# neodk_v1_2.net
KiCad netlist of a schematic drawn in EAGLE
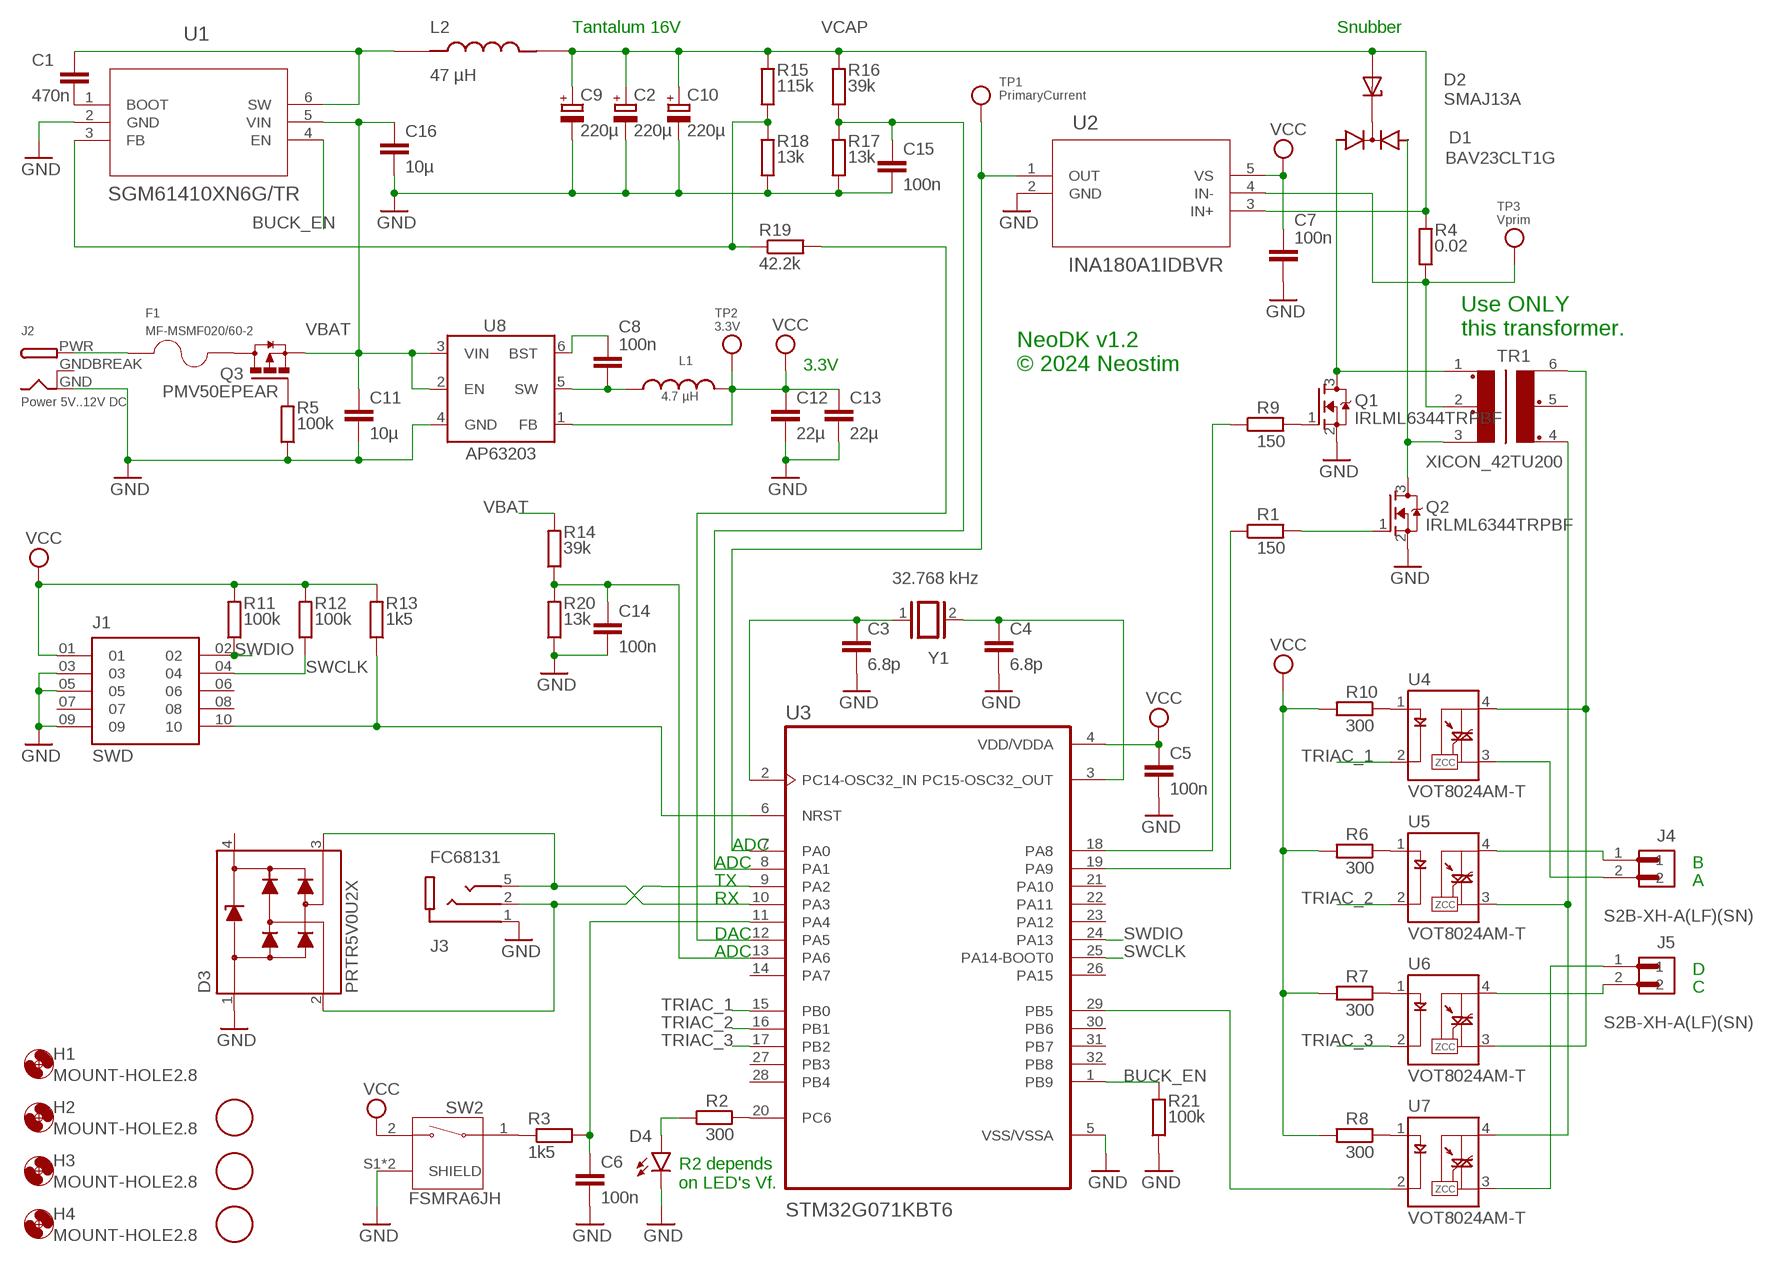
[diagram p0: schematic, sheet 1]

(export (version "E")
  (design (tool "Eeschema 10.0.6"))
  (components
    (comp (ref "C1")
      (value "470n")
      (footprint "eagle-import:C0603")
      (libsource (lib "eagle-import") (part "C-EUC0603"))
    )
    (comp (ref "C2")
      (value "220µ")
      (footprint "eagle-import:SMC_D")
      (fields (field (name "MP") "TPSE227M016R0150"))
      (libsource (lib "eagle-import") (part "CPOL-EUSMCD"))
    )
    (comp (ref "C3")
      (value "6.8p")
      (footprint "eagle-import:C0603")
      (libsource (lib "eagle-import") (part "C-EUC0603"))
    )
    (comp (ref "C4")
      (value "6.8p")
      (footprint "eagle-import:C0603")
      (libsource (lib "eagle-import") (part "C-EUC0603"))
    )
    (comp (ref "C5")
      (value "100n")
      (footprint "eagle-import:C0603")
      (libsource (lib "eagle-import") (part "C-EUC0603"))
    )
    (comp (ref "C6")
      (value "100n")
      (footprint "eagle-import:C0603")
      (libsource (lib "eagle-import") (part "C-EUC0603"))
    )
    (comp (ref "C7")
      (value "100n")
      (footprint "eagle-import:C0603")
      (libsource (lib "eagle-import") (part "C-EUC0603"))
    )
    (comp (ref "C8")
      (value "100n")
      (footprint "eagle-import:C0603")
      (libsource (lib "eagle-import") (part "C-EUC0603"))
    )
    (comp (ref "C9")
      (value "220µ")
      (footprint "eagle-import:SMC_D")
      (fields (field (name "MP") "TPSE227M016R0150"))
      (libsource (lib "eagle-import") (part "CPOL-EUSMCD"))
    )
    (comp (ref "C10")
      (value "220µ")
      (footprint "eagle-import:SMC_D")
      (fields (field (name "MP") "TPSE227M016R0150"))
      (libsource (lib "eagle-import") (part "CPOL-EUSMCD"))
    )
    (comp (ref "C11")
      (value "10µ")
      (footprint "eagle-import:C0603")
      (libsource (lib "eagle-import") (part "C-EUC0603"))
    )
    (comp (ref "C12")
      (value "22µ")
      (footprint "eagle-import:C0603")
      (libsource (lib "eagle-import") (part "C-EUC0603"))
    )
    (comp (ref "C13")
      (value "22µ")
      (footprint "eagle-import:C0603")
      (libsource (lib "eagle-import") (part "C-EUC0603"))
    )
    (comp (ref "C14")
      (value "100n")
      (footprint "eagle-import:C0603")
      (libsource (lib "eagle-import") (part "C-EUC0603"))
    )
    (comp (ref "C15")
      (value "100n")
      (footprint "eagle-import:C0603")
      (libsource (lib "eagle-import") (part "C-EUC0603"))
    )
    (comp (ref "C16")
      (value "10µ")
      (footprint "eagle-import:C0603")
      (libsource (lib "eagle-import") (part "C-EUC0603"))
    )
    (comp (ref "D1")
      (value "BAV23CLT1G")
      (footprint "eagle-import:SOT23")
      (libsource (lib "eagle-import") (part "DIODE-2AC|CASOT23"))
    )
    (comp (ref "D2")
      (value "SMAJ13A")
      (footprint "eagle-import:DIOM4325X250N")
      (fields (field (name "MF") "STMicroelectronics") (field (name "MP") "SMAJ13A-TR"))
      (libsource (lib "eagle-import") (part "SMAJ13A"))
    )
    (comp (ref "D3")
      (value "PRTR5V0U2X")
      (footprint "eagle-import:SOT190P230X110-4N")
      (fields (field (name "MF") "Nexperia USA"))
      (libsource (lib "eagle-import") (part "PRTR5V0U2X"))
    )
    (comp (ref "D4")
      (value "LEDCHIP-LED0805")
      (footprint "eagle-import:CHIP-LED0805")
      (libsource (lib "eagle-import") (part "LEDCHIP-LED0805"))
    )
    (comp (ref "F1")
      (value "MF-MSMF020/60-2")
      (footprint "eagle-import:FUSER_MF-MSMF020_60-2")
      (fields (field (name "MF") "Bourns"))
      (libsource (lib "eagle-import") (part "MF-MSMF020/60-2"))
    )
    (comp (ref "FID1")
      (value "FIDUCIAL")
      (footprint "eagle-import:FIDUCIAL_1MM")
      (libsource (lib "eagle-import") (part "FIDUCIAL"))
    )
    (comp (ref "FID2")
      (value "FIDUCIAL")
      (footprint "eagle-import:FIDUCIAL_1MM")
      (libsource (lib "eagle-import") (part "FIDUCIAL"))
    )
    (comp (ref "FID3")
      (value "FIDUCIAL")
      (footprint "eagle-import:FIDUCIAL_1MM")
      (libsource (lib "eagle-import") (part "FIDUCIAL"))
    )
    (comp (ref "H1")
      (value "MOUNT-HOLE2.8")
      (footprint "eagle-import:2,8")
      (libsource (lib "eagle-import") (part "MOUNT-HOLE2.8"))
    )
    (comp (ref "H2")
      (value "MOUNT-HOLE2.8")
      (footprint "eagle-import:2,8")
      (libsource (lib "eagle-import") (part "MOUNT-HOLE2.8"))
    )
    (comp (ref "H3")
      (value "MOUNT-HOLE2.8")
      (footprint "eagle-import:2,8")
      (libsource (lib "eagle-import") (part "MOUNT-HOLE2.8"))
    )
    (comp (ref "H4")
      (value "MOUNT-HOLE2.8")
      (footprint "eagle-import:2,8")
      (libsource (lib "eagle-import") (part "MOUNT-HOLE2.8"))
    )
    (comp (ref "J1")
      (value "SWD")
      (footprint "eagle-import:SAMTEC_FTSH-105-XX-X-DV")
      (fields (field (name "MF") "Samtec") (field (name "MP") "FTSH-105-01-L-DV"))
      (libsource (lib "eagle-import") (part "FTSH-105-XX-X-DV"))
    )
    (comp (ref "J2")
      (value "Power 5V..12V DC")
      (footprint "eagle-import:DCJACK_2MM_PTH")
      (libsource (lib "eagle-import") (part "DCBARRELPTH"))
    )
    (comp (ref "J3")
      (value "FC68131")
      (footprint "eagle-import:CLIFF_FC68131")
      (fields (field (name "MF") "Cliff"))
      (libsource (lib "eagle-import") (part "FC68131"))
    )
    (comp (ref "J4")
      (value "S2B-XH-A(LF)(SN)")
      (footprint "eagle-import:JST_S2B-XH-A(LF)(SN)")
      (fields (field (name "MF") "JST Sales"))
      (libsource (lib "eagle-import") (part "S2B-XH-A(LF)(SN)"))
    )
    (comp (ref "J5")
      (value "S2B-XH-A(LF)(SN)")
      (footprint "eagle-import:JST_S2B-XH-A(LF)(SN)")
      (fields (field (name "MF") "JST Sales"))
      (libsource (lib "eagle-import") (part "S2B-XH-A(LF)(SN)"))
    )
    (comp (ref "L1")
      (value "4.7 µH")
      (footprint "eagle-import:IND_VLS5045EX-4R7M")
      (fields (field (name "MF") "TDK") (field (name "MP") "VLS5045EX-4R7M"))
      (libsource (lib "eagle-import") (part "VLS5045EX-4R7M"))
    )
    (comp (ref "L2")
      (value "47 µH")
      (footprint "eagle-import:IND_CLF7045NIT-470M-D")
      (fields (field (name "MF") "TDK") (field (name "MP") "CLF7045NIT-470M-D"))
      (libsource (lib "eagle-import") (part "CLF7045NIT-470M-D"))
    )
    (comp (ref "Q1")
      (value "IRLML6344TRPBF")
      (footprint "eagle-import:SOT23")
      (libsource (lib "eagle-import") (part "MOSFET-NREFLOW"))
    )
    (comp (ref "Q2")
      (value "IRLML6344TRPBF")
      (footprint "eagle-import:SOT23")
      (libsource (lib "eagle-import") (part "MOSFET-NREFLOW"))
    )
    (comp (ref "Q3")
      (value "PMV50EPEAR")
      (footprint "eagle-import:SOT23")
      (libsource (lib "eagle-import") (part "PMV50EPEAR"))
    )
    (comp (ref "R1")
      (value "150")
      (footprint "eagle-import:R0603")
      (libsource (lib "eagle-import") (part "R-EU_R0603"))
    )
    (comp (ref "R2")
      (value "300")
      (footprint "eagle-import:R0603")
      (libsource (lib "eagle-import") (part "R-EU_R0603"))
    )
    (comp (ref "R3")
      (value "1k5")
      (footprint "eagle-import:R0603")
      (libsource (lib "eagle-import") (part "R-EU_R0603"))
    )
    (comp (ref "R4")
      (value "0.02")
      (footprint "eagle-import:R1206")
      (libsource (lib "eagle-import") (part "R-EU_R1206"))
    )
    (comp (ref "R5")
      (value "100k")
      (footprint "eagle-import:R0603")
      (libsource (lib "eagle-import") (part "R-EU_R0603"))
    )
    (comp (ref "R6")
      (value "300")
      (footprint "eagle-import:R0603")
      (libsource (lib "eagle-import") (part "R-EU_R0603"))
    )
    (comp (ref "R7")
      (value "300")
      (footprint "eagle-import:R0603")
      (libsource (lib "eagle-import") (part "R-EU_R0603"))
    )
    (comp (ref "R8")
      (value "300")
      (footprint "eagle-import:R0603")
      (libsource (lib "eagle-import") (part "R-EU_R0603"))
    )
    (comp (ref "R9")
      (value "150")
      (footprint "eagle-import:R0603")
      (libsource (lib "eagle-import") (part "R-EU_R0603"))
    )
    (comp (ref "R10")
      (value "300")
      (footprint "eagle-import:R0603")
      (libsource (lib "eagle-import") (part "R-EU_R0603"))
    )
    (comp (ref "R11")
      (value "100k")
      (footprint "eagle-import:R0603")
      (libsource (lib "eagle-import") (part "R-EU_R0603"))
    )
    (comp (ref "R12")
      (value "100k")
      (footprint "eagle-import:R0603")
      (libsource (lib "eagle-import") (part "R-EU_R0603"))
    )
    (comp (ref "R13")
      (value "1k5")
      (footprint "eagle-import:R0603")
      (libsource (lib "eagle-import") (part "R-EU_R0603"))
    )
    (comp (ref "R14")
      (value "39k")
      (footprint "eagle-import:R0603")
      (libsource (lib "eagle-import") (part "R-EU_R0603"))
    )
    (comp (ref "R15")
      (value "115k")
      (footprint "eagle-import:R0603")
      (libsource (lib "eagle-import") (part "R-EU_R0603"))
    )
    (comp (ref "R16")
      (value "39k")
      (footprint "eagle-import:R0603")
      (libsource (lib "eagle-import") (part "R-EU_R0603"))
    )
    (comp (ref "R17")
      (value "13k")
      (footprint "eagle-import:R0603")
      (libsource (lib "eagle-import") (part "R-EU_R0603"))
    )
    (comp (ref "R18")
      (value "13k")
      (footprint "eagle-import:R0603")
      (libsource (lib "eagle-import") (part "R-EU_R0603"))
    )
    (comp (ref "R19")
      (value "42.2k")
      (footprint "eagle-import:R0603")
      (libsource (lib "eagle-import") (part "R-EU_R0603"))
    )
    (comp (ref "R20")
      (value "13k")
      (footprint "eagle-import:R0603")
      (libsource (lib "eagle-import") (part "R-EU_R0603"))
    )
    (comp (ref "R21")
      (value "100k")
      (footprint "eagle-import:R0603")
      (libsource (lib "eagle-import") (part "R-EU_R0603"))
    )
    (comp (ref "SW2")
      (value "FSMRA6JH")
      (footprint "eagle-import:TE_FSMRA6JH")
      (fields (field (name "MF") "TE Connectivity"))
      (libsource (lib "eagle-import") (part "FSMRA6JH"))
    )
    (comp (ref "TP1")
      (value "PrimaryCurrent")
      (footprint "eagle-import:TESTPOINT_ROUND_1MM")
      (libsource (lib "eagle-import") (part "TESTPOINTROUND1MM"))
    )
    (comp (ref "TP2")
      (value "3.3V")
      (footprint "eagle-import:TESTPOINT_ROUND_1MM")
      (libsource (lib "eagle-import") (part "TESTPOINTROUND1MM"))
    )
    (comp (ref "TP3")
      (value "Vprim")
      (footprint "eagle-import:TESTPOINT_ROUND_1MM")
      (libsource (lib "eagle-import") (part "TESTPOINTROUND1MM"))
    )
    (comp (ref "TR1")
      (value "XICON_42TU200")
      (footprint "eagle-import:42TUXXX")
      (libsource (lib "eagle-import") (part "XICON_42TU200"))
    )
    (comp (ref "U1")
      (value "SGM61410XN6G/TR")
      (footprint "eagle-import:SOT-23-6_SNC")
      (libsource (lib "eagle-import") (part "SGM61410XN6G/TR"))
    )
    (comp (ref "U2")
      (value "INA180A1IDBVR")
      (footprint "eagle-import:DBV5")
      (libsource (lib "eagle-import") (part "INA180A1IDBVR"))
    )
    (comp (ref "U3")
      (value "STM32G071KBT6")
      (footprint "eagle-import:QFP80P900X900X160-32N")
      (fields (field (name "MF") "STMicroelectronics") (field (name "MP") "STM32G070KBT6"))
      (libsource (lib "eagle-import") (part "STM32G071KBT6"))
    )
    (comp (ref "U4")
      (value "VOT8024AM-T")
      (footprint "eagle-import:SOP254P675X240-4N")
      (fields (field (name "MF") "Vishay Semiconductor Opto Division"))
      (libsource (lib "eagle-import") (part "VOT8024AM-T"))
    )
    (comp (ref "U5")
      (value "VOT8024AM-T")
      (footprint "eagle-import:SOP254P675X240-4N")
      (fields (field (name "MF") "Vishay Semiconductor Opto Division"))
      (libsource (lib "eagle-import") (part "VOT8024AM-T"))
    )
    (comp (ref "U6")
      (value "VOT8024AM-T")
      (footprint "eagle-import:SOP254P675X240-4N")
      (fields (field (name "MF") "Vishay Semiconductor Opto Division"))
      (libsource (lib "eagle-import") (part "VOT8024AM-T"))
    )
    (comp (ref "U7")
      (value "VOT8024AM-T")
      (footprint "eagle-import:SOP254P675X240-4N")
      (fields (field (name "MF") "Vishay Semiconductor Opto Division"))
      (libsource (lib "eagle-import") (part "VOT8024AM-T"))
    )
    (comp (ref "U8")
      (value "AP63203")
      (footprint "eagle-import:SOT23-6")
      (fields (field (name "MF") "Diodes Zetex"))
      (libsource (lib "eagle-import") (part "AP63203"))
    )
    (comp (ref "Y1")
      (value "32.768 kHz")
      (footprint "eagle-import:XTAL_NX3215SA-32.768K-STD-MUA-8")
      (fields (field (name "MF") "NDK America,") (field (name "MP") "NX3215SA-32.768K-STD-MUA-8"))
      (libsource (lib "eagle-import") (part "NX3215SA-32.768K-STD-MUA-8"))
    )
  )
  (nets
    (net (code "1") (name "/BUCK_EN") (class "Default")
      (node (ref "R21") (pin "2") (pinfunction "2_2") (pintype "passive"))
      (node (ref "U1") (pin "4") (pinfunction "EN_4") (pintype "passive"))
      (node (ref "U3") (pin "1") (pinfunction "PB9_1") (pintype "bidirectional"))
    )
    (net (code "2") (name "/GNDBREAK") (class "Default")
      (node (ref "J2") (pin "GNDBREAK") (pinfunction "GNDBREAK_GNDBREAK") (pintype "power_in"))
    )
    (net (code "3") (name "/SWCLK") (class "Default")
      (node (ref "J1") (pin "04") (pinfunction "04_04") (pintype "passive"))
      (node (ref "R12") (pin "1") (pinfunction "1_1") (pintype "passive"))
      (node (ref "U3") (pin "25") (pinfunction "PA14-BOOT0_25") (pintype "bidirectional"))
    )
    (net (code "4") (name "/SWDIO") (class "Default")
      (node (ref "J1") (pin "02") (pinfunction "02_02") (pintype "passive"))
      (node (ref "R11") (pin "1") (pinfunction "1_1") (pintype "passive"))
      (node (ref "U3") (pin "24") (pinfunction "PA13_24") (pintype "bidirectional"))
    )
    (net (code "5") (name "/TRIAC_1") (class "Default")
      (node (ref "U3") (pin "15") (pinfunction "PB0_15") (pintype "bidirectional"))
      (node (ref "U4") (pin "2") (pinfunction "C_2") (pintype "passive"))
    )
    (net (code "6") (name "/TRIAC_2") (class "Default")
      (node (ref "U3") (pin "16") (pinfunction "PB1_16") (pintype "bidirectional"))
      (node (ref "U5") (pin "2") (pinfunction "C_2") (pintype "passive"))
    )
    (net (code "7") (name "/TRIAC_3") (class "Default")
      (node (ref "U3") (pin "17") (pinfunction "PB2_17") (pintype "bidirectional"))
      (node (ref "U6") (pin "2") (pinfunction "C_2") (pintype "passive"))
    )
    (net (code "8") (name "/VBAT") (class "Default")
      (node (ref "C11") (pin "1") (pinfunction "1_1") (pintype "passive"))
      (node (ref "C16") (pin "1") (pinfunction "1_1") (pintype "passive"))
      (node (ref "Q3") (pin "3") (pinfunction "S_3") (pintype "passive"))
      (node (ref "R14") (pin "2") (pinfunction "2_2") (pintype "passive"))
      (node (ref "U1") (pin "5") (pinfunction "VIN_5") (pintype "power_in"))
      (node (ref "U8") (pin "2") (pinfunction "EN_2") (pintype "bidirectional"))
      (node (ref "U8") (pin "3") (pinfunction "VIN_3") (pintype "bidirectional"))
    )
    (net (code "9") (name "/VCAP") (class "Default")
      (node (ref "C10") (pin "+") (pinfunction "+_+") (pintype "passive"))
      (node (ref "C2") (pin "+") (pinfunction "+_+") (pintype "passive"))
      (node (ref "C9") (pin "+") (pinfunction "+_+") (pintype "passive"))
      (node (ref "D2") (pin "A") (pinfunction "A_A") (pintype "passive"))
      (node (ref "L2") (pin "2") (pinfunction "2_2") (pintype "passive"))
      (node (ref "R15") (pin "2") (pinfunction "2_2") (pintype "passive"))
      (node (ref "R16") (pin "2") (pinfunction "2_2") (pintype "passive"))
      (node (ref "R4") (pin "2") (pinfunction "2_2") (pintype "passive"))
      (node (ref "U2") (pin "3") (pinfunction "IN+_3") (pintype "input"))
    )
    (net (code "10") (name "GND") (class "Default")
      (node (ref "C10") (pin "-") (pinfunction "-_-") (pintype "passive"))
      (node (ref "C11") (pin "2") (pinfunction "2_2") (pintype "passive"))
      (node (ref "C12") (pin "2") (pinfunction "2_2") (pintype "passive"))
      (node (ref "C13") (pin "2") (pinfunction "2_2") (pintype "passive"))
      (node (ref "C14") (pin "2") (pinfunction "2_2") (pintype "passive"))
      (node (ref "C15") (pin "2") (pinfunction "2_2") (pintype "passive"))
      (node (ref "C16") (pin "2") (pinfunction "2_2") (pintype "passive"))
      (node (ref "C2") (pin "-") (pinfunction "-_-") (pintype "passive"))
      (node (ref "C3") (pin "2") (pinfunction "2_2") (pintype "passive"))
      (node (ref "C4") (pin "2") (pinfunction "2_2") (pintype "passive"))
      (node (ref "C5") (pin "2") (pinfunction "2_2") (pintype "passive"))
      (node (ref "C6") (pin "2") (pinfunction "2_2") (pintype "passive"))
      (node (ref "C7") (pin "2") (pinfunction "2_2") (pintype "passive"))
      (node (ref "C9") (pin "-") (pinfunction "-_-") (pintype "passive"))
      (node (ref "D3") (pin "1") (pinfunction "GND_1") (pintype "passive"))
      (node (ref "D4") (pin "C") (pinfunction "C_C") (pintype "passive"))
      (node (ref "J1") (pin "03") (pinfunction "03_03") (pintype "passive"))
      (node (ref "J1") (pin "05") (pinfunction "05_05") (pintype "passive"))
      (node (ref "J1") (pin "09") (pinfunction "09_09") (pintype "passive"))
      (node (ref "J2") (pin "GND") (pinfunction "GND_GND") (pintype "power_in"))
      (node (ref "J3") (pin "1") (pinfunction "SLEEVE_1") (pintype "passive"))
      (node (ref "Q1") (pin "2") (pinfunction "S_2") (pintype "bidirectional"))
      (node (ref "Q2") (pin "2") (pinfunction "S_2") (pintype "bidirectional"))
      (node (ref "R17") (pin "1") (pinfunction "1_1") (pintype "passive"))
      (node (ref "R18") (pin "1") (pinfunction "1_1") (pintype "passive"))
      (node (ref "R20") (pin "1") (pinfunction "1_1") (pintype "passive"))
      (node (ref "R21") (pin "1") (pinfunction "1_1") (pintype "passive"))
      (node (ref "R5") (pin "1") (pinfunction "1_1") (pintype "passive"))
      (node (ref "SW2") (pin "S1") (pinfunction "SHIELD_S1") (pintype "passive"))
      (node (ref "SW2") (pin "S2") (pinfunction "SHIELD_S2") (pintype "passive"))
      (node (ref "U1") (pin "2") (pinfunction "GND_2") (pintype "passive"))
      (node (ref "U2") (pin "2") (pinfunction "GND_2") (pintype "power_in"))
      (node (ref "U3") (pin "5") (pinfunction "VSS/VSSA_5") (pintype "power_in"))
      (node (ref "U8") (pin "4") (pinfunction "GND_4") (pintype "bidirectional"))
    )
    (net (code "11") (name "Net-(D1-A1)") (class "Default")
      (node (ref "D1") (pin "1") (pinfunction "A1_1") (pintype "passive"))
      (node (ref "Q1") (pin "3") (pinfunction "D_3") (pintype "bidirectional"))
      (node (ref "TR1") (pin "1") (pinfunction "1_1") (pintype "passive"))
    )
    (net (code "12") (name "Net-(D1-A2)") (class "Default")
      (node (ref "D1") (pin "2") (pinfunction "A2_2") (pintype "passive"))
      (node (ref "Q2") (pin "3") (pinfunction "D_3") (pintype "bidirectional"))
      (node (ref "TR1") (pin "3") (pinfunction "3_3") (pintype "passive"))
    )
    (net (code "13") (name "Net-(D1-C)") (class "Default")
      (node (ref "D1") (pin "3") (pinfunction "C_3") (pintype "passive"))
      (node (ref "D2") (pin "C") (pinfunction "C_C") (pintype "passive"))
    )
    (net (code "14") (name "Net-(D3-I{slash}O_1)") (class "Default")
      (node (ref "D3") (pin "2") (pinfunction "I/O_1_2") (pintype "passive"))
      (node (ref "J3") (pin "2") (pinfunction "RING_2") (pintype "passive"))
      (node (ref "U3") (pin "9") (pinfunction "PA2_9") (pintype "bidirectional"))
    )
    (net (code "15") (name "Net-(D3-I{slash}O_2)") (class "Default")
      (node (ref "D3") (pin "3") (pinfunction "I/O_2_3") (pintype "passive"))
      (node (ref "J3") (pin "5") (pinfunction "TIP_5") (pintype "passive"))
      (node (ref "U3") (pin "10") (pinfunction "PA3_10") (pintype "bidirectional"))
    )
    (net (code "16") (name "Net-(D4-PadA)") (class "Default")
      (node (ref "D4") (pin "A") (pinfunction "A_A") (pintype "passive"))
      (node (ref "R2") (pin "1") (pinfunction "1_1") (pintype "passive"))
    )
    (net (code "17") (name "Net-(F1-Pad1)") (class "Default")
      (node (ref "F1") (pin "1") (pinfunction "1_1") (pintype "passive"))
      (node (ref "J2") (pin "PWR") (pinfunction "PWR_PWR") (pintype "power_in"))
    )
    (net (code "18") (name "Net-(Q1-G)") (class "Default")
      (node (ref "Q1") (pin "1") (pinfunction "G_1") (pintype "bidirectional"))
      (node (ref "R9") (pin "2") (pinfunction "2_2") (pintype "passive"))
    )
    (net (code "19") (name "Net-(Q2-G)") (class "Default")
      (node (ref "Q2") (pin "1") (pinfunction "G_1") (pintype "bidirectional"))
      (node (ref "R1") (pin "2") (pinfunction "2_2") (pintype "passive"))
    )
    (net (code "20") (name "Net-(Q3-D)") (class "Default")
      (node (ref "F1") (pin "2") (pinfunction "2_2") (pintype "passive"))
      (node (ref "Q3") (pin "2") (pinfunction "D_2") (pintype "passive"))
    )
    (net (code "21") (name "Net-(Q3-G)") (class "Default")
      (node (ref "Q3") (pin "1") (pinfunction "G_1") (pintype "passive"))
      (node (ref "R5") (pin "2") (pinfunction "2_2") (pintype "passive"))
    )
    (net (code "22") (name "Net-(R3-Pad1)") (class "Default")
      (node (ref "R3") (pin "1") (pinfunction "1_1") (pintype "passive"))
      (node (ref "SW2") (pin "1") (pinfunction "1_1") (pintype "passive"))
    )
    (net (code "23") (name "Net-(U1-BOOT)") (class "Default")
      (node (ref "C1") (pin "2") (pinfunction "2_2") (pintype "passive"))
      (node (ref "U1") (pin "1") (pinfunction "BOOT_1") (pintype "passive"))
    )
    (net (code "24") (name "Net-(U1-FB)") (class "Default")
      (node (ref "R15") (pin "1") (pinfunction "1_1") (pintype "passive"))
      (node (ref "R18") (pin "2") (pinfunction "2_2") (pintype "passive"))
      (node (ref "R19") (pin "1") (pinfunction "1_1") (pintype "passive"))
      (node (ref "U1") (pin "3") (pinfunction "FB_3") (pintype "passive"))
    )
    (net (code "25") (name "Net-(U1-SW)") (class "Default")
      (node (ref "C1") (pin "1") (pinfunction "1_1") (pintype "passive"))
      (node (ref "L2") (pin "1") (pinfunction "1_1") (pintype "passive"))
      (node (ref "U1") (pin "6") (pinfunction "SW_6") (pintype "output"))
    )
    (net (code "26") (name "Net-(U2-IN-)") (class "Default")
      (node (ref "R4") (pin "1") (pinfunction "1_1") (pintype "passive"))
      (node (ref "TP3") (pin "P$1") (pinfunction "P$1_P$1") (pintype "bidirectional"))
      (node (ref "TR1") (pin "2") (pinfunction "2_2") (pintype "passive"))
      (node (ref "U2") (pin "4") (pinfunction "IN-_4") (pintype "input"))
    )
    (net (code "27") (name "Net-(U2-OUT)") (class "Default")
      (node (ref "TP1") (pin "P$1") (pinfunction "P$1_P$1") (pintype "bidirectional"))
      (node (ref "U2") (pin "1") (pinfunction "OUT_1") (pintype "output"))
      (node (ref "U3") (pin "7") (pinfunction "PA0_7") (pintype "bidirectional"))
    )
    (net (code "28") (name "Net-(U3-NRST)") (class "Default")
      (node (ref "J1") (pin "10") (pinfunction "10_10") (pintype "passive"))
      (node (ref "R13") (pin "1") (pinfunction "1_1") (pintype "passive"))
      (node (ref "U3") (pin "6") (pinfunction "NRST_6") (pintype "bidirectional"))
    )
    (net (code "29") (name "Net-(U3-PA1)") (class "Default")
      (node (ref "C15") (pin "1") (pinfunction "1_1") (pintype "passive"))
      (node (ref "R16") (pin "1") (pinfunction "1_1") (pintype "passive"))
      (node (ref "R17") (pin "2") (pinfunction "2_2") (pintype "passive"))
      (node (ref "U3") (pin "8") (pinfunction "PA1_8") (pintype "bidirectional"))
    )
    (net (code "30") (name "Net-(U3-PA4)") (class "Default")
      (node (ref "C6") (pin "1") (pinfunction "1_1") (pintype "passive"))
      (node (ref "R3") (pin "2") (pinfunction "2_2") (pintype "passive"))
      (node (ref "U3") (pin "11") (pinfunction "PA4_11") (pintype "bidirectional"))
    )
    (net (code "31") (name "Net-(U3-PA5)") (class "Default")
      (node (ref "R19") (pin "2") (pinfunction "2_2") (pintype "passive"))
      (node (ref "U3") (pin "12") (pinfunction "PA5_12") (pintype "bidirectional"))
    )
    (net (code "32") (name "Net-(U3-PA6)") (class "Default")
      (node (ref "C14") (pin "1") (pinfunction "1_1") (pintype "passive"))
      (node (ref "R14") (pin "1") (pinfunction "1_1") (pintype "passive"))
      (node (ref "R20") (pin "2") (pinfunction "2_2") (pintype "passive"))
      (node (ref "U3") (pin "13") (pinfunction "PA6_13") (pintype "bidirectional"))
    )
    (net (code "33") (name "Net-(U3-PA8)") (class "Default")
      (node (ref "R9") (pin "1") (pinfunction "1_1") (pintype "passive"))
      (node (ref "U3") (pin "18") (pinfunction "PA8_18") (pintype "bidirectional"))
    )
    (net (code "34") (name "Net-(U3-PA9)") (class "Default")
      (node (ref "R1") (pin "1") (pinfunction "1_1") (pintype "passive"))
      (node (ref "U3") (pin "19") (pinfunction "PA9_19") (pintype "bidirectional"))
    )
    (net (code "35") (name "Net-(U3-PB5)") (class "Default")
      (node (ref "U3") (pin "29") (pinfunction "PB5_29") (pintype "bidirectional"))
      (node (ref "U7") (pin "2") (pinfunction "C_2") (pintype "passive"))
    )
    (net (code "36") (name "Net-(U3-PC6)") (class "Default")
      (node (ref "R2") (pin "2") (pinfunction "2_2") (pintype "passive"))
      (node (ref "U3") (pin "20") (pinfunction "PC6_20") (pintype "bidirectional"))
    )
    (net (code "37") (name "Net-(U3-PC14-OSC32_IN)") (class "Default")
      (node (ref "C3") (pin "1") (pinfunction "1_1") (pintype "passive"))
      (node (ref "U3") (pin "2") (pinfunction "PC14-OSC32_IN_2") (pintype "input"))
      (node (ref "Y1") (pin "1") (pinfunction "1_1") (pintype "passive"))
    )
    (net (code "38") (name "Net-(U3-PC15-OSC32_OUT)") (class "Default")
      (node (ref "C4") (pin "1") (pinfunction "1_1") (pintype "passive"))
      (node (ref "U3") (pin "3") (pinfunction "PC15-OSC32_OUT_3") (pintype "output"))
      (node (ref "Y1") (pin "2") (pinfunction "2_2") (pintype "passive"))
    )
    (net (code "39") (name "Net-(U4-A)") (class "Default")
      (node (ref "R10") (pin "1") (pinfunction "1_1") (pintype "passive"))
      (node (ref "U4") (pin "1") (pinfunction "A_1") (pintype "passive"))
    )
    (net (code "40") (name "Net-(U4-MT1)") (class "Default")
      (node (ref "J4") (pin "2") (pinfunction "2_2") (pintype "passive"))
      (node (ref "U4") (pin "3") (pinfunction "MT1_3") (pintype "passive"))
    )
    (net (code "41") (name "Net-(U4-MT2)") (class "Default")
      (node (ref "TR1") (pin "6") (pinfunction "6_6") (pintype "passive"))
      (node (ref "U4") (pin "4") (pinfunction "MT2_4") (pintype "passive"))
      (node (ref "U6") (pin "3") (pinfunction "MT1_3") (pintype "passive"))
    )
    (net (code "42") (name "Net-(U5-A)") (class "Default")
      (node (ref "R6") (pin "1") (pinfunction "1_1") (pintype "passive"))
      (node (ref "U5") (pin "1") (pinfunction "A_1") (pintype "passive"))
    )
    (net (code "43") (name "Net-(U5-MT1)") (class "Default")
      (node (ref "TR1") (pin "4") (pinfunction "4_4") (pintype "passive"))
      (node (ref "U5") (pin "3") (pinfunction "MT1_3") (pintype "passive"))
      (node (ref "U7") (pin "4") (pinfunction "MT2_4") (pintype "passive"))
    )
    (net (code "44") (name "Net-(U5-MT2)") (class "Default")
      (node (ref "J4") (pin "1") (pinfunction "1_1") (pintype "passive"))
      (node (ref "U5") (pin "4") (pinfunction "MT2_4") (pintype "passive"))
    )
    (net (code "45") (name "Net-(U6-A)") (class "Default")
      (node (ref "R7") (pin "1") (pinfunction "1_1") (pintype "passive"))
      (node (ref "U6") (pin "1") (pinfunction "A_1") (pintype "passive"))
    )
    (net (code "46") (name "Net-(U6-MT2)") (class "Default")
      (node (ref "J5") (pin "2") (pinfunction "2_2") (pintype "passive"))
      (node (ref "U6") (pin "4") (pinfunction "MT2_4") (pintype "passive"))
    )
    (net (code "47") (name "Net-(U7-A)") (class "Default")
      (node (ref "R8") (pin "1") (pinfunction "1_1") (pintype "passive"))
      (node (ref "U7") (pin "1") (pinfunction "A_1") (pintype "passive"))
    )
    (net (code "48") (name "Net-(U7-MT1)") (class "Default")
      (node (ref "J5") (pin "1") (pinfunction "1_1") (pintype "passive"))
      (node (ref "U7") (pin "3") (pinfunction "MT1_3") (pintype "passive"))
    )
    (net (code "49") (name "Net-(U8-BST)") (class "Default")
      (node (ref "C8") (pin "1") (pinfunction "1_1") (pintype "passive"))
      (node (ref "U8") (pin "6") (pinfunction "BST_6") (pintype "bidirectional"))
    )
    (net (code "50") (name "Net-(U8-SW)") (class "Default")
      (node (ref "C8") (pin "2") (pinfunction "2_2") (pintype "passive"))
      (node (ref "L1") (pin "1") (pinfunction "1_1") (pintype "passive"))
      (node (ref "U8") (pin "5") (pinfunction "SW_5") (pintype "bidirectional"))
    )
    (net (code "51") (name "VCC") (class "Default")
      (node (ref "C12") (pin "1") (pinfunction "1_1") (pintype "passive"))
      (node (ref "C13") (pin "1") (pinfunction "1_1") (pintype "passive"))
      (node (ref "C5") (pin "1") (pinfunction "1_1") (pintype "passive"))
      (node (ref "C7") (pin "1") (pinfunction "1_1") (pintype "passive"))
      (node (ref "J1") (pin "01") (pinfunction "01_01") (pintype "passive"))
      (node (ref "L1") (pin "2") (pinfunction "2_2") (pintype "passive"))
      (node (ref "R10") (pin "2") (pinfunction "2_2") (pintype "passive"))
      (node (ref "R11") (pin "2") (pinfunction "2_2") (pintype "passive"))
      (node (ref "R12") (pin "2") (pinfunction "2_2") (pintype "passive"))
      (node (ref "R13") (pin "2") (pinfunction "2_2") (pintype "passive"))
      (node (ref "R6") (pin "2") (pinfunction "2_2") (pintype "passive"))
      (node (ref "R7") (pin "2") (pinfunction "2_2") (pintype "passive"))
      (node (ref "R8") (pin "2") (pinfunction "2_2") (pintype "passive"))
      (node (ref "SW2") (pin "2") (pinfunction "2_2") (pintype "passive"))
      (node (ref "TP2") (pin "P$1") (pinfunction "P$1_P$1") (pintype "bidirectional"))
      (node (ref "U2") (pin "5") (pinfunction "VS_5") (pintype "power_in"))
      (node (ref "U3") (pin "4") (pinfunction "VDD/VDDA_4") (pintype "power_in"))
      (node (ref "U8") (pin "1") (pinfunction "FB_1") (pintype "bidirectional"))
    )
    (net (code "52") (name "unconnected-(D3-VCC-Pad4)") (class "Default")
      (node (ref "D3") (pin "4") (pinfunction "VCC_4") (pintype "passive"))
    )
    (net (code "53") (name "unconnected-(J1-Pad06)") (class "Default")
      (node (ref "J1") (pin "06") (pinfunction "06_06") (pintype "passive"))
    )
    (net (code "54") (name "unconnected-(J1-Pad07)") (class "Default")
      (node (ref "J1") (pin "07") (pinfunction "07_07") (pintype "passive"))
    )
    (net (code "55") (name "unconnected-(J1-Pad08)") (class "Default")
      (node (ref "J1") (pin "08") (pinfunction "08_08") (pintype "passive"))
    )
    (net (code "56") (name "unconnected-(TR1-Pad5)") (class "Default")
      (node (ref "TR1") (pin "5") (pinfunction "5_5") (pintype "passive"))
    )
    (net (code "57") (name "unconnected-(U3-PA7-Pad14)") (class "Default")
      (node (ref "U3") (pin "14") (pinfunction "PA7_14") (pintype "bidirectional"))
    )
    (net (code "58") (name "unconnected-(U3-PA10-Pad21)") (class "Default")
      (node (ref "U3") (pin "21") (pinfunction "PA10_21") (pintype "bidirectional"))
    )
    (net (code "59") (name "unconnected-(U3-PA11-Pad22)") (class "Default")
      (node (ref "U3") (pin "22") (pinfunction "PA11_22") (pintype "bidirectional"))
    )
    (net (code "60") (name "unconnected-(U3-PA12-Pad23)") (class "Default")
      (node (ref "U3") (pin "23") (pinfunction "PA12_23") (pintype "bidirectional"))
    )
    (net (code "61") (name "unconnected-(U3-PA15-Pad26)") (class "Default")
      (node (ref "U3") (pin "26") (pinfunction "PA15_26") (pintype "bidirectional"))
    )
    (net (code "62") (name "unconnected-(U3-PB3-Pad27)") (class "Default")
      (node (ref "U3") (pin "27") (pinfunction "PB3_27") (pintype "bidirectional"))
    )
    (net (code "63") (name "unconnected-(U3-PB4-Pad28)") (class "Default")
      (node (ref "U3") (pin "28") (pinfunction "PB4_28") (pintype "bidirectional"))
    )
    (net (code "64") (name "unconnected-(U3-PB6-Pad30)") (class "Default")
      (node (ref "U3") (pin "30") (pinfunction "PB6_30") (pintype "bidirectional"))
    )
    (net (code "65") (name "unconnected-(U3-PB7-Pad31)") (class "Default")
      (node (ref "U3") (pin "31") (pinfunction "PB7_31") (pintype "bidirectional"))
    )
    (net (code "66") (name "unconnected-(U3-PB8-Pad32)") (class "Default")
      (node (ref "U3") (pin "32") (pinfunction "PB8_32") (pintype "bidirectional"))
    )
  )
)
